# Sheet_4_-_Capteurs.net
KiCad netlist of a schematic drawn in Altium Designer
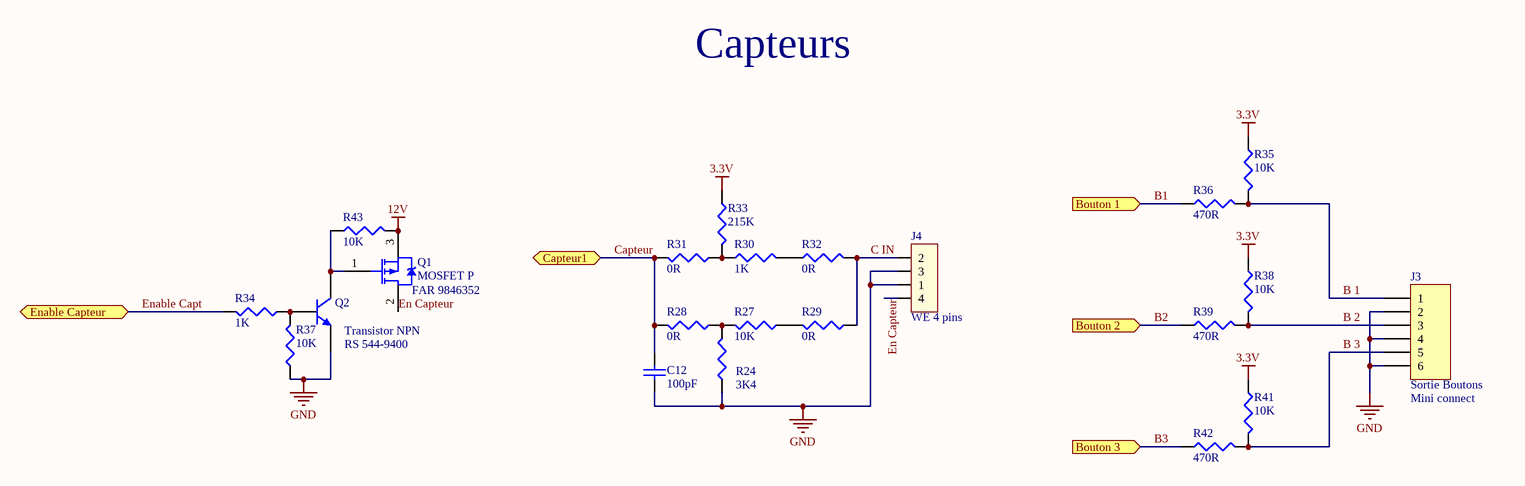
[diagram p0: Sheet 4 - Capteurs.SchDoc]

(export (version "E")
  (design (tool "Eeschema 10.0.6"))
  (components
    (comp (ref "C12")
      (value "100pF")
      (footprint "pcb_peb_1:C0805")
      (description "Capacitor 0805")
      (fields (field (name "PUBLISHER") "Altium Limited"))
      (libsource (lib "Miscellaneous Devices") (part "Cap"))
    )
    (comp (ref "J3")
      (value "Mini connect")
      (footprint "690367280676")
      (description "Header, 6-Pin")
      (fields (field (name "VALUE1") "Sortie Boutons") (field (name "PUBLISHER") "Altium Limited"))
      (libsource (lib "Miscellaneous Connectors") (part "MHDR1X6"))
    )
    (comp (ref "J4")
      (value "WE 4 pins")
      (footprint "690367280476")
      (description "connecteur WE")
      (libsource (lib "lib_peb_1") (part "MICRO-MATCH FOB.04P"))
    )
    (comp (ref "Q1")
      (value "MOSFET P")
      (footprint "SOT-23")
      (description "P-Channel Power MOSFET")
      (fields (field (name "RÉFÉRENCE COMMANDE") "FAR 9846352") (field (name "PUBLISHER") "Altium Limited"))
      (libsource (lib "Miscellaneous Devices") (part "PMOS-2"))
    )
    (comp (ref "Q2")
      (value "Transistor NPN")
      (footprint "SOT23_L")
      (description "NPN Bipolar Transistor")
      (fields (field (name "RÉFÉRENCE COMMANDE") "RS 544-9400") (field (name "PUBLISHER") "Altium Limited"))
      (libsource (lib "Miscellaneous Devices") (part "QNPN"))
    )
    (comp (ref "R24")
      (value "3K4")
      (footprint "0805")
      (description "Resistor 0805")
      (fields (field (name "PUBLISHER") "Altium Limited"))
      (libsource (lib "Miscellaneous Devices") (part "Res3"))
    )
    (comp (ref "R27")
      (value "10K")
      (footprint "0805")
      (description "Resistor 0805")
      (fields (field (name "PUBLISHER") "Altium Limited"))
      (libsource (lib "Miscellaneous Devices") (part "Res3"))
    )
    (comp (ref "R28")
      (value "0R")
      (footprint "0805")
      (description "Resistor 0805")
      (fields (field (name "PUBLISHER") "Altium Limited"))
      (libsource (lib "Miscellaneous Devices") (part "Res3"))
    )
    (comp (ref "R29")
      (value "0R")
      (footprint "0805")
      (description "Resistor 0805")
      (fields (field (name "PUBLISHER") "Altium Limited"))
      (libsource (lib "Miscellaneous Devices") (part "Res3"))
    )
    (comp (ref "R30")
      (value "1K")
      (footprint "0805")
      (description "Resistor 0805")
      (fields (field (name "PUBLISHER") "Altium Limited"))
      (libsource (lib "Miscellaneous Devices") (part "Res3"))
    )
    (comp (ref "R31")
      (value "0R")
      (footprint "0805")
      (description "Resistor 0805")
      (fields (field (name "PUBLISHER") "Altium Limited"))
      (libsource (lib "Miscellaneous Devices") (part "Res3"))
    )
    (comp (ref "R32")
      (value "0R")
      (footprint "0805")
      (description "Resistor 0805")
      (fields (field (name "PUBLISHER") "Altium Limited"))
      (libsource (lib "Miscellaneous Devices") (part "Res3"))
    )
    (comp (ref "R33")
      (value "215K")
      (footprint "0805")
      (description "Resistor 0805")
      (fields (field (name "PUBLISHER") "Altium Limited"))
      (libsource (lib "Miscellaneous Devices") (part "Res3"))
    )
    (comp (ref "R34")
      (value "1K")
      (footprint "0805")
      (description "Resistor 0805")
      (fields (field (name "PUBLISHER") "Altium Limited"))
      (libsource (lib "Miscellaneous Devices") (part "Res3"))
    )
    (comp (ref "R35")
      (value "10K")
      (footprint "0805")
      (description "Resistor 0805")
      (fields (field (name "PUBLISHER") "Altium Limited"))
      (libsource (lib "Miscellaneous Devices") (part "Res3"))
    )
    (comp (ref "R36")
      (value "470R")
      (footprint "0805")
      (description "Resistor 0805")
      (fields (field (name "PUBLISHER") "Altium Limited"))
      (libsource (lib "Miscellaneous Devices") (part "Res3"))
    )
    (comp (ref "R37")
      (value "10K")
      (footprint "0805")
      (description "Resistor 0805")
      (fields (field (name "PUBLISHER") "Altium Limited"))
      (libsource (lib "Miscellaneous Devices") (part "Res3"))
    )
    (comp (ref "R38")
      (value "10K")
      (footprint "0805")
      (description "Resistor 0805")
      (fields (field (name "PUBLISHER") "Altium Limited"))
      (libsource (lib "Miscellaneous Devices") (part "Res3"))
    )
    (comp (ref "R39")
      (value "470R")
      (footprint "0805")
      (description "Resistor 0805")
      (fields (field (name "PUBLISHER") "Altium Limited"))
      (libsource (lib "Miscellaneous Devices") (part "Res3"))
    )
    (comp (ref "R41")
      (value "10K")
      (footprint "0805")
      (description "Resistor 0805")
      (fields (field (name "PUBLISHER") "Altium Limited"))
      (libsource (lib "Miscellaneous Devices") (part "Res3"))
    )
    (comp (ref "R42")
      (value "470R")
      (footprint "0805")
      (description "Resistor 0805")
      (fields (field (name "PUBLISHER") "Altium Limited"))
      (libsource (lib "Miscellaneous Devices") (part "Res3"))
    )
    (comp (ref "R43")
      (value "10K")
      (footprint "0805")
      (description "Resistor 0805")
      (fields (field (name "PUBLISHER") "Altium Limited"))
      (libsource (lib "Miscellaneous Devices") (part "Res3"))
    )
  )
  (nets
    (net (code "1") (name "/B 1") (class "Default")
      (node (ref "J3") (pin "1") (pinfunction "1_1") (pintype "passive"))
      (node (ref "R35") (pin "2") (pinfunction "2_2") (pintype "passive"))
      (node (ref "R36") (pin "2") (pinfunction "2_2") (pintype "passive"))
    )
    (net (code "2") (name "/B 2") (class "Default")
      (node (ref "J3") (pin "3") (pinfunction "3_3") (pintype "passive"))
      (node (ref "R38") (pin "2") (pinfunction "2_2") (pintype "passive"))
      (node (ref "R39") (pin "2") (pinfunction "2_2") (pintype "passive"))
    )
    (net (code "3") (name "/B 3") (class "Default")
      (node (ref "J3") (pin "5") (pinfunction "5_5") (pintype "passive"))
      (node (ref "R41") (pin "2") (pinfunction "2_2") (pintype "passive"))
      (node (ref "R42") (pin "2") (pinfunction "2_2") (pintype "passive"))
    )
    (net (code "4") (name "/B1") (class "Default")
      (node (ref "R36") (pin "1") (pinfunction "1_1") (pintype "passive"))
    )
    (net (code "5") (name "/B2") (class "Default")
      (node (ref "R39") (pin "1") (pinfunction "1_1") (pintype "passive"))
    )
    (net (code "6") (name "/B3") (class "Default")
      (node (ref "R42") (pin "1") (pinfunction "1_1") (pintype "passive"))
    )
    (net (code "7") (name "/C IN") (class "Default")
      (node (ref "J4") (pin "2") (pinfunction "2_2") (pintype "passive"))
      (node (ref "R29") (pin "1") (pinfunction "1_1") (pintype "passive"))
      (node (ref "R32") (pin "2") (pinfunction "2_2") (pintype "passive"))
    )
    (net (code "8") (name "/Capteur") (class "Default")
      (node (ref "C12") (pin "1") (pinfunction "1_1") (pintype "passive"))
      (node (ref "R28") (pin "2") (pinfunction "2_2") (pintype "passive"))
      (node (ref "R31") (pin "2") (pinfunction "2_2") (pintype "passive"))
    )
    (net (code "9") (name "/En Capteur") (class "Default")
      (node (ref "J4") (pin "4") (pinfunction "4_4") (pintype "passive"))
      (node (ref "Q1") (pin "2") (pinfunction "D_2") (pintype "passive"))
    )
    (net (code "10") (name "/Enable Capt") (class "Default")
      (node (ref "R34") (pin "2") (pinfunction "2_2") (pintype "passive"))
    )
    (net (code "11") (name "3.3V") (class "Default")
      (node (ref "R33") (pin "1") (pinfunction "1_1") (pintype "passive"))
      (node (ref "R35") (pin "1") (pinfunction "1_1") (pintype "passive"))
      (node (ref "R38") (pin "1") (pinfunction "1_1") (pintype "passive"))
      (node (ref "R41") (pin "1") (pinfunction "1_1") (pintype "passive"))
    )
    (net (code "12") (name "12V") (class "Default")
      (node (ref "Q1") (pin "3") (pinfunction "S_3") (pintype "passive"))
      (node (ref "R43") (pin "2") (pinfunction "2_2") (pintype "passive"))
    )
    (net (code "13") (name "GND") (class "Default")
      (node (ref "C12") (pin "2") (pinfunction "2_2") (pintype "passive"))
      (node (ref "J3") (pin "2") (pinfunction "2_2") (pintype "passive"))
      (node (ref "J3") (pin "4") (pinfunction "4_4") (pintype "passive"))
      (node (ref "J3") (pin "6") (pinfunction "6_6") (pintype "passive"))
      (node (ref "J4") (pin "1") (pinfunction "1_1") (pintype "passive"))
      (node (ref "J4") (pin "3") (pinfunction "3_3") (pintype "passive"))
      (node (ref "Q2") (pin "2") (pinfunction "E_2") (pintype "passive"))
      (node (ref "R24") (pin "1") (pinfunction "1_1") (pintype "passive"))
      (node (ref "R37") (pin "1") (pinfunction "1_1") (pintype "passive"))
    )
    (net (code "14") (name "Net-(Q1-G)") (class "Default")
      (node (ref "Q1") (pin "1") (pinfunction "G_1") (pintype "passive"))
      (node (ref "Q2") (pin "3") (pinfunction "C_3") (pintype "passive"))
      (node (ref "R43") (pin "1") (pinfunction "1_1") (pintype "passive"))
    )
    (net (code "15") (name "Net-(Q2-B)") (class "Default")
      (node (ref "Q2") (pin "1") (pinfunction "B_1") (pintype "passive"))
      (node (ref "R34") (pin "1") (pinfunction "1_1") (pintype "passive"))
      (node (ref "R37") (pin "2") (pinfunction "2_2") (pintype "passive"))
    )
    (net (code "16") (name "Net-(R24-Pad2)") (class "Default")
      (node (ref "R24") (pin "2") (pinfunction "2_2") (pintype "passive"))
      (node (ref "R27") (pin "2") (pinfunction "2_2") (pintype "passive"))
      (node (ref "R28") (pin "1") (pinfunction "1_1") (pintype "passive"))
    )
    (net (code "17") (name "Net-(R27-Pad1)") (class "Default")
      (node (ref "R27") (pin "1") (pinfunction "1_1") (pintype "passive"))
      (node (ref "R29") (pin "2") (pinfunction "2_2") (pintype "passive"))
    )
    (net (code "18") (name "Net-(R30-Pad1)") (class "Default")
      (node (ref "R30") (pin "1") (pinfunction "1_1") (pintype "passive"))
      (node (ref "R31") (pin "1") (pinfunction "1_1") (pintype "passive"))
      (node (ref "R33") (pin "2") (pinfunction "2_2") (pintype "passive"))
    )
    (net (code "19") (name "Net-(R30-Pad2)") (class "Default")
      (node (ref "R30") (pin "2") (pinfunction "2_2") (pintype "passive"))
      (node (ref "R32") (pin "1") (pinfunction "1_1") (pintype "passive"))
    )
  )
)
